# tricorder-featherwing-mk-1_5.net
KiCad netlist of a schematic drawn in EAGLE
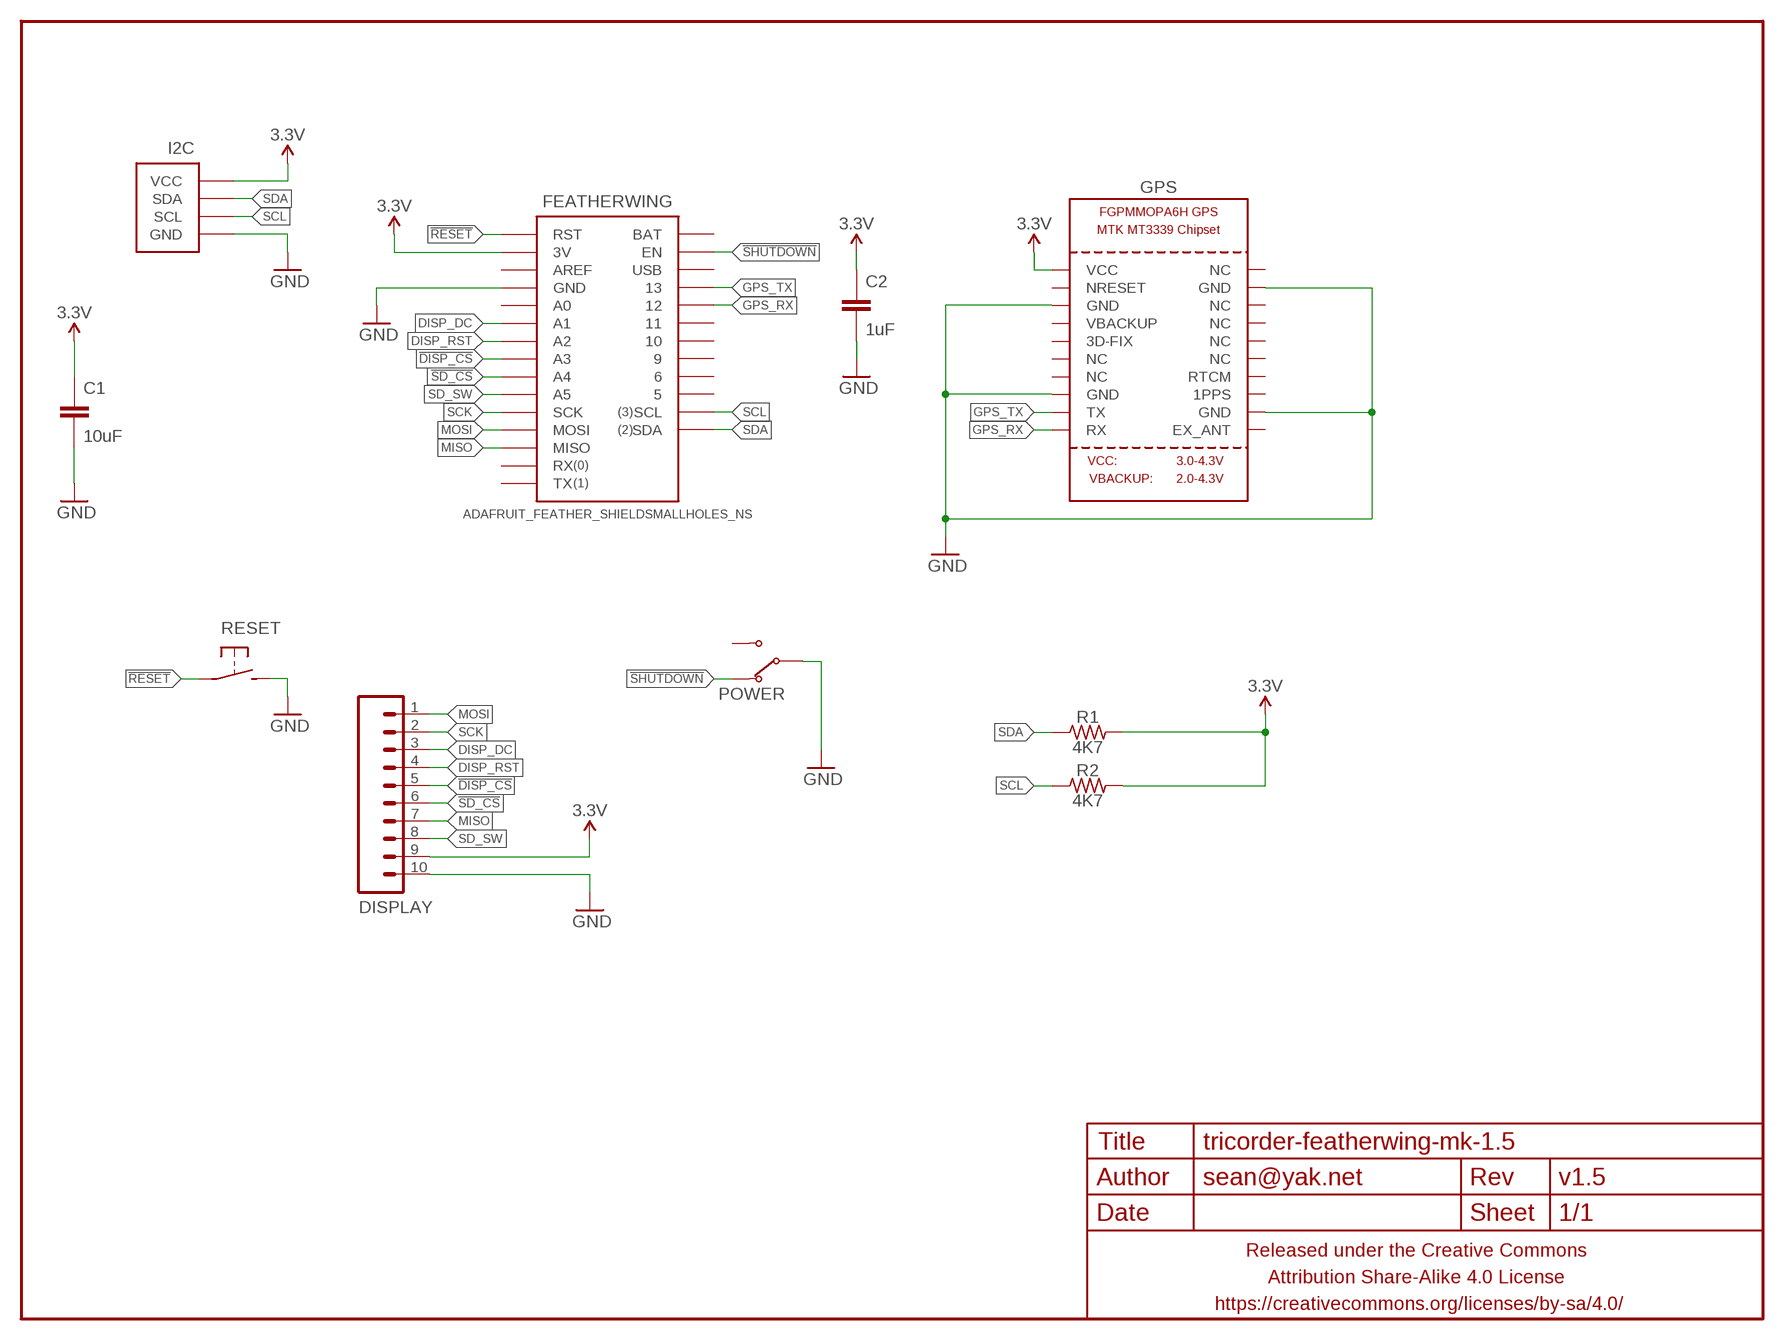
[diagram p0: schematic, sheet 1]

(export (version "E")
  (design (tool "Eeschema 10.0.6"))
  (components
    (comp (ref "C1")
      (value "10uF")
      (footprint "eagle-import:C1210")
      (libsource (lib "eagle-import") (part "CAPACITOR-CERAMICC1210"))
    )
    (comp (ref "C2")
      (value "1uF")
      (footprint "eagle-import:C0603")
      (libsource (lib "eagle-import") (part "CAPACITOR-CERAMICC0603"))
    )
    (comp (ref "DISPLAY")
      (value "M102MM")
      (footprint "eagle-import:1X10-2MM")
      (libsource (lib "eagle-import") (part "M102MM"))
    )
    (comp (ref "FEATHERWING")
      (value "ADAFRUIT_FEATHER_SHIELDSMALLHOLES_NS")
      (footprint "eagle-import:ADAFRUIT_FEATHER_SMALLHOLES_NS")
      (libsource (lib "eagle-import") (part "ADAFRUIT_FEATHER_SHIELDSMALLHOLES_NS"))
    )
    (comp (ref "FRAME1")
      (value "FRAME-LETTERNO_PACKAGE")
      (footprint "eagle-import:DUMMY")
      (fields (field (name "DESIGNER") "sean@yak.net") (field (name "VERSION") "v1.5"))
      (libsource (lib "eagle-import") (part "FRAME-LETTERNO_PACKAGE"))
    )
    (comp (ref "GPS")
      (value "GPS_FGPMMOPA6H")
      (footprint "eagle-import:FGPMMOPA6H")
      (libsource (lib "eagle-import") (part "GPS_FGPMMOPA6H"))
    )
    (comp (ref "I2C")
      (value "M04-I2CPTH-2MM-CENTERED")
      (footprint "eagle-import:1X04-2MM-CENTERED-I2C")
      (libsource (lib "eagle-import") (part "M04-I2CPTH-2MM-CENTERED"))
    )
    (comp (ref "POWER")
      (value "SWITCH-SPDTPCM12SMTR")
      (footprint "eagle-import:SWITCH-SPDT-SMD-RA-PCM12SMTR")
      (libsource (lib "eagle-import") (part "SWITCH-SPDTPCM12SMTR"))
    )
    (comp (ref "R1")
      (value "4K7")
      (footprint "eagle-import:R0603")
      (libsource (lib "eagle-import") (part "RESISTORR0603"))
    )
    (comp (ref "R2")
      (value "4K7")
      (footprint "eagle-import:R0603")
      (libsource (lib "eagle-import") (part "RESISTORR0603"))
    )
    (comp (ref "RESET")
      (value "SPST-NO-TACTCK-PTS840-GK")
      (footprint "eagle-import:TACTILE-SMD-CK-PTS840-GK")
      (libsource (lib "eagle-import") (part "SPST-NO-TACTCK-PTS840-GK"))
    )
  )
  (nets
    (net (code "1") (name "/~{DISP_CS}") (class "Default")
      (node (ref "DISPLAY") (pin "5") (pinfunction "5_5") (pintype "passive"))
      (node (ref "FEATHERWING") (pin "A3") (pinfunction "A3_A3") (pintype "bidirectional"))
    )
    (net (code "2") (name "/~{RESET}") (class "Default")
      (node (ref "FEATHERWING") (pin "RST") (pinfunction "RST_RST") (pintype "bidirectional"))
      (node (ref "RESET") (pin "1") (pinfunction "1_1") (pintype "passive"))
      (node (ref "RESET") (pin "2") (pinfunction "1_2") (pintype "passive"))
    )
    (net (code "3") (name "/~{SD_CS}") (class "Default")
      (node (ref "DISPLAY") (pin "6") (pinfunction "6_6") (pintype "passive"))
      (node (ref "FEATHERWING") (pin "A4") (pinfunction "A4_A4") (pintype "bidirectional"))
    )
    (net (code "4") (name "/~{SHUTDOWN}") (class "Default")
      (node (ref "FEATHERWING") (pin "EN") (pinfunction "EN_EN") (pintype "bidirectional"))
      (node (ref "POWER") (pin "1") (pinfunction "NC_1") (pintype "passive"))
    )
    (net (code "5") (name "3.3V") (class "Default")
      (node (ref "C1") (pin "1") (pinfunction "1_1") (pintype "passive"))
      (node (ref "C2") (pin "1") (pinfunction "1_1") (pintype "passive"))
      (node (ref "DISPLAY") (pin "9") (pinfunction "9_9") (pintype "passive"))
      (node (ref "FEATHERWING") (pin "3V") (pinfunction "3V_3V") (pintype "bidirectional"))
      (node (ref "GPS") (pin "P$1") (pinfunction "VCC_P$1") (pintype "bidirectional"))
      (node (ref "I2C") (pin "2") (pinfunction "VCC_2") (pintype "bidirectional"))
      (node (ref "R1") (pin "2") (pinfunction "2_2") (pintype "passive"))
      (node (ref "R2") (pin "2") (pinfunction "2_2") (pintype "passive"))
    )
    (net (code "6") (name "DISP_DC") (class "Default")
      (node (ref "DISPLAY") (pin "3") (pinfunction "3_3") (pintype "passive"))
      (node (ref "FEATHERWING") (pin "A1") (pinfunction "A1_A1") (pintype "bidirectional"))
    )
    (net (code "7") (name "DISP_RST") (class "Default")
      (node (ref "DISPLAY") (pin "4") (pinfunction "4_4") (pintype "passive"))
      (node (ref "FEATHERWING") (pin "A2") (pinfunction "A2_A2") (pintype "bidirectional"))
    )
    (net (code "8") (name "GND") (class "Default")
      (node (ref "C1") (pin "2") (pinfunction "2_2") (pintype "passive"))
      (node (ref "C2") (pin "2") (pinfunction "2_2") (pintype "passive"))
      (node (ref "DISPLAY") (pin "10") (pinfunction "10_10") (pintype "passive"))
      (node (ref "FEATHERWING") (pin "GND@0") (pinfunction "GND_GND@0") (pintype "bidirectional"))
      (node (ref "FEATHERWING") (pin "GND@1") (pinfunction "GND_GND@1") (pintype "bidirectional"))
      (node (ref "GPS") (pin "P$12") (pinfunction "GND_P$12") (pintype "bidirectional"))
      (node (ref "GPS") (pin "P$19") (pinfunction "GND_P$19") (pintype "bidirectional"))
      (node (ref "GPS") (pin "P$3") (pinfunction "GND_P$3") (pintype "bidirectional"))
      (node (ref "GPS") (pin "P$8") (pinfunction "GND_P$8") (pintype "bidirectional"))
      (node (ref "I2C") (pin "1") (pinfunction "GND_1") (pintype "bidirectional"))
      (node (ref "POWER") (pin "2") (pinfunction "COM_2") (pintype "passive"))
      (node (ref "RESET") (pin "3") (pinfunction "2_3") (pintype "passive"))
      (node (ref "RESET") (pin "4") (pinfunction "2_4") (pintype "passive"))
    )
    (net (code "9") (name "GPS_RX") (class "Default")
      (node (ref "FEATHERWING") (pin "12") (pinfunction "12_12") (pintype "bidirectional"))
      (node (ref "GPS") (pin "P$10") (pinfunction "RX_P$10") (pintype "bidirectional"))
    )
    (net (code "10") (name "GPS_TX") (class "Default")
      (node (ref "FEATHERWING") (pin "13") (pinfunction "13_13") (pintype "bidirectional"))
      (node (ref "GPS") (pin "P$9") (pinfunction "TX_P$9") (pintype "bidirectional"))
    )
    (net (code "11") (name "MISO") (class "Default")
      (node (ref "DISPLAY") (pin "7") (pinfunction "7_7") (pintype "passive"))
      (node (ref "FEATHERWING") (pin "MISO") (pinfunction "MISO_MISO") (pintype "bidirectional"))
    )
    (net (code "12") (name "MOSI") (class "Default")
      (node (ref "DISPLAY") (pin "1") (pinfunction "1_1") (pintype "passive"))
      (node (ref "FEATHERWING") (pin "MOSI") (pinfunction "MOSI_MOSI") (pintype "bidirectional"))
    )
    (net (code "13") (name "SCK") (class "Default")
      (node (ref "DISPLAY") (pin "2") (pinfunction "2_2") (pintype "passive"))
      (node (ref "FEATHERWING") (pin "SCK") (pinfunction "SCK_SCK") (pintype "bidirectional"))
    )
    (net (code "14") (name "SCL") (class "Default")
      (node (ref "FEATHERWING") (pin "SCL") (pinfunction "SCL_SCL") (pintype "bidirectional"))
      (node (ref "I2C") (pin "4") (pinfunction "SCL_4") (pintype "bidirectional"))
      (node (ref "R2") (pin "1") (pinfunction "1_1") (pintype "passive"))
    )
    (net (code "15") (name "SDA") (class "Default")
      (node (ref "FEATHERWING") (pin "SDA") (pinfunction "SDA_SDA") (pintype "bidirectional"))
      (node (ref "I2C") (pin "3") (pinfunction "SDA_3") (pintype "bidirectional"))
      (node (ref "R1") (pin "1") (pinfunction "1_1") (pintype "passive"))
    )
    (net (code "16") (name "SD_SW") (class "Default")
      (node (ref "DISPLAY") (pin "8") (pinfunction "8_8") (pintype "passive"))
      (node (ref "FEATHERWING") (pin "A5") (pinfunction "A5_A5") (pintype "bidirectional"))
    )
    (net (code "17") (name "unconnected-(FEATHERWING-Pad5)") (class "Default")
      (node (ref "FEATHERWING") (pin "5") (pinfunction "5_5") (pintype "bidirectional"))
    )
    (net (code "18") (name "unconnected-(FEATHERWING-Pad6)") (class "Default")
      (node (ref "FEATHERWING") (pin "6") (pinfunction "6_6") (pintype "bidirectional"))
    )
    (net (code "19") (name "unconnected-(FEATHERWING-Pad9)") (class "Default")
      (node (ref "FEATHERWING") (pin "9") (pinfunction "9_9") (pintype "bidirectional"))
    )
    (net (code "20") (name "unconnected-(FEATHERWING-Pad10)") (class "Default")
      (node (ref "FEATHERWING") (pin "10") (pinfunction "10_10") (pintype "bidirectional"))
    )
    (net (code "21") (name "unconnected-(FEATHERWING-Pad11)") (class "Default")
      (node (ref "FEATHERWING") (pin "11") (pinfunction "11_11") (pintype "bidirectional"))
    )
    (net (code "22") (name "unconnected-(FEATHERWING-PadA0)") (class "Default")
      (node (ref "FEATHERWING") (pin "A0") (pinfunction "A0_A0") (pintype "bidirectional"))
    )
    (net (code "23") (name "unconnected-(FEATHERWING-PadAREF)") (class "Default")
      (node (ref "FEATHERWING") (pin "AREF") (pinfunction "AREF_AREF") (pintype "bidirectional"))
    )
    (net (code "24") (name "unconnected-(FEATHERWING-PadBAT)") (class "Default")
      (node (ref "FEATHERWING") (pin "BAT") (pinfunction "BAT_BAT") (pintype "bidirectional"))
    )
    (net (code "25") (name "unconnected-(FEATHERWING-PadRX)") (class "Default")
      (node (ref "FEATHERWING") (pin "RX") (pinfunction "RX_RX") (pintype "bidirectional"))
    )
    (net (code "26") (name "unconnected-(FEATHERWING-PadTX)") (class "Default")
      (node (ref "FEATHERWING") (pin "TX") (pinfunction "TX_TX") (pintype "bidirectional"))
    )
    (net (code "27") (name "unconnected-(FEATHERWING-PadUSB)") (class "Default")
      (node (ref "FEATHERWING") (pin "USB") (pinfunction "USB_USB") (pintype "bidirectional"))
    )
    (net (code "28") (name "unconnected-(GPS-1PPS-PadP$13)") (class "Default")
      (node (ref "GPS") (pin "P$13") (pinfunction "1PPS_P$13") (pintype "bidirectional"))
    )
    (net (code "29") (name "unconnected-(GPS-3D-FIX-PadP$5)") (class "Default")
      (node (ref "GPS") (pin "P$5") (pinfunction "3D-FIX_P$5") (pintype "bidirectional"))
    )
    (net (code "30") (name "unconnected-(GPS-EX_ANT-PadP$11)") (class "Default")
      (node (ref "GPS") (pin "P$11") (pinfunction "EX_ANT_P$11") (pintype "bidirectional"))
    )
    (net (code "31") (name "unconnected-(GPS-NC-PadP$6)") (class "Default")
      (node (ref "GPS") (pin "P$6") (pinfunction "NC_P$6") (pintype "bidirectional"))
    )
    (net (code "32") (name "unconnected-(GPS-NC-PadP$7)") (class "Default")
      (node (ref "GPS") (pin "P$7") (pinfunction "NC_P$7") (pintype "bidirectional"))
    )
    (net (code "33") (name "unconnected-(GPS-NC-PadP$15)") (class "Default")
      (node (ref "GPS") (pin "P$15") (pinfunction "NC_P$15") (pintype "bidirectional"))
    )
    (net (code "34") (name "unconnected-(GPS-NC-PadP$16)") (class "Default")
      (node (ref "GPS") (pin "P$16") (pinfunction "NC_P$16") (pintype "bidirectional"))
    )
    (net (code "35") (name "unconnected-(GPS-NC-PadP$17)") (class "Default")
      (node (ref "GPS") (pin "P$17") (pinfunction "NC_P$17") (pintype "bidirectional"))
    )
    (net (code "36") (name "unconnected-(GPS-NC-PadP$18)") (class "Default")
      (node (ref "GPS") (pin "P$18") (pinfunction "NC_P$18") (pintype "bidirectional"))
    )
    (net (code "37") (name "unconnected-(GPS-NC-PadP$20)") (class "Default")
      (node (ref "GPS") (pin "P$20") (pinfunction "NC_P$20") (pintype "bidirectional"))
    )
    (net (code "38") (name "unconnected-(GPS-NRESET-PadP$2)") (class "Default")
      (node (ref "GPS") (pin "P$2") (pinfunction "NRESET_P$2") (pintype "bidirectional"))
    )
    (net (code "39") (name "unconnected-(GPS-RTCM-PadP$14)") (class "Default")
      (node (ref "GPS") (pin "P$14") (pinfunction "RTCM_P$14") (pintype "bidirectional"))
    )
    (net (code "40") (name "unconnected-(GPS-VBACKUP-PadP$4)") (class "Default")
      (node (ref "GPS") (pin "P$4") (pinfunction "VBACKUP_P$4") (pintype "bidirectional"))
    )
    (net (code "41") (name "unconnected-(POWER-NO-Pad3)") (class "Default")
      (node (ref "POWER") (pin "3") (pinfunction "NO_3") (pintype "passive"))
    )
  )
)
